# 05_Mechanicals.net
KiCad netlist of a schematic drawn in Altium Designer
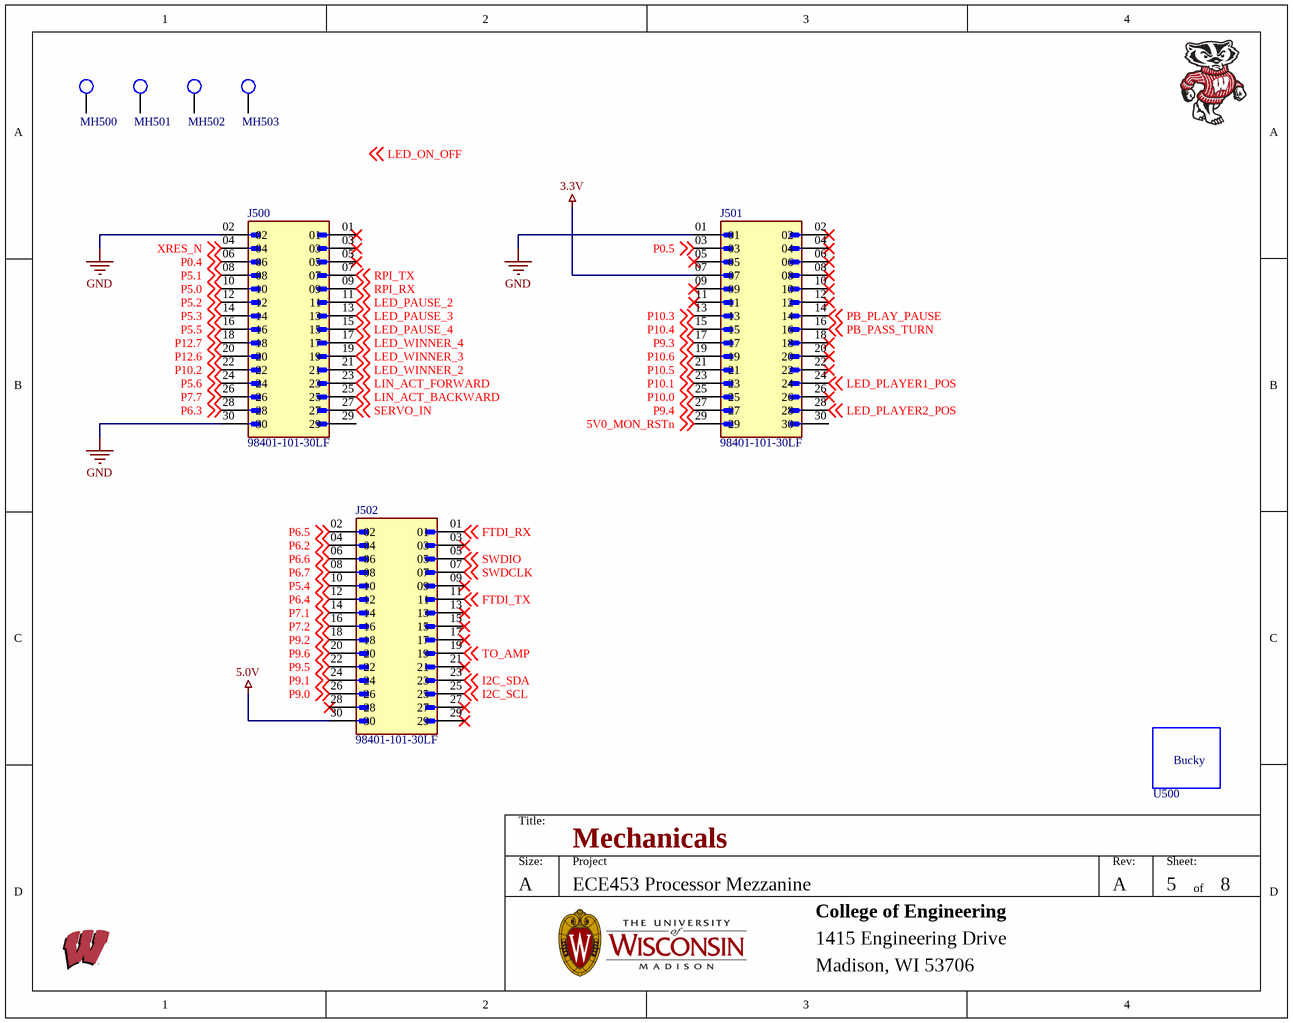
[diagram p0: 05_Mechanicals.SchDoc]

(export (version "E")
  (design (tool "Eeschema 10.0.6"))
  (components
    (comp (ref "J500")
      (value "98401-101-30LF")
      (footprint "AMPHENOL_98401-101-30LF")
      (description "Conn Unshrouded Header HDR 30 POS 2.54mm Solder ST SMD T/R")
      (fields (field (name "MF") "Amphenol ICC (FCI)") (field (name "MANUFACTURER") "Amphenol ICC / FCI"))
      (libsource (lib "98401-101-30LF") (part "98401-101-30LF"))
    )
    (comp (ref "J501")
      (value "98401-101-30LF")
      (footprint "AMPHENOL_98401-101-30LF")
      (description "Conn Unshrouded Header HDR 30 POS 2.54mm Solder ST SMD T/R")
      (fields (field (name "MF") "Amphenol ICC (FCI)") (field (name "MANUFACTURER") "Amphenol ICC / FCI"))
      (libsource (lib "98401-101-30LF") (part "98401-101-30LF"))
    )
    (comp (ref "J502")
      (value "98401-101-30LF")
      (footprint "AMPHENOL_98401-101-30LF")
      (description "Conn Unshrouded Header HDR 30 POS 2.54mm Solder ST SMD T/R")
      (fields (field (name "MF") "Amphenol ICC (FCI)") (field (name "MANUFACTURER") "Amphenol ICC / FCI"))
      (libsource (lib "98401-101-30LF") (part "98401-101-30LF"))
    )
    (comp (ref "MH500")
      (value "MHOLE_2_55MM")
      (footprint "MHOLE_2_55MM")
      (description "Mounting Holde")
      (fields (field (name "MANUFACTURER PART NUMBER") "UW MTHOLE"))
      (libsource (lib "ece315-2018-fall") (part "MHOLE_2_55MM"))
    )
    (comp (ref "MH501")
      (value "MHOLE_2_55MM")
      (footprint "MHOLE_2_55MM")
      (description "Mounting Holde")
      (fields (field (name "MANUFACTURER PART NUMBER") "UW MTHOLE"))
      (libsource (lib "ece315-2018-fall") (part "MHOLE_2_55MM"))
    )
    (comp (ref "MH502")
      (value "MHOLE_2_55MM")
      (footprint "MHOLE_2_55MM")
      (description "Mounting Holde")
      (fields (field (name "MANUFACTURER PART NUMBER") "UW MTHOLE"))
      (libsource (lib "ece315-2018-fall") (part "MHOLE_2_55MM"))
    )
    (comp (ref "MH503")
      (value "MHOLE_2_55MM")
      (footprint "MHOLE_2_55MM")
      (description "Mounting Holde")
      (fields (field (name "MANUFACTURER PART NUMBER") "UW MTHOLE"))
      (libsource (lib "ece315-2018-fall") (part "MHOLE_2_55MM"))
    )
    (comp (ref "U500")
      (value "Bucky")
      (footprint "WalkingBucky")
      (description "Bucky Badger Image")
      (fields (field (name "MANUFACTURER PART NUMBER") "UW Bucky"))
      (libsource (lib "ECE453") (part "Bucky"))
    )
  )
  (nets
    (net (code "1") (name "3.3V") (class "Default")
      (node (ref "J501") (pin "07") (pinfunction "07_07") (pintype "passive"))
    )
    (net (code "2") (name "5.0V") (class "Default")
      (node (ref "J502") (pin "30") (pinfunction "30_30") (pintype "passive"))
    )
    (net (code "3") (name "5V0_MON_RSTn") (class "Default")
      (node (ref "J501") (pin "29") (pinfunction "29_29") (pintype "passive"))
    )
    (net (code "4") (name "FTDI_RX") (class "Default")
      (node (ref "J502") (pin "01") (pinfunction "01_01") (pintype "passive"))
    )
    (net (code "5") (name "FTDI_TX") (class "Default")
      (node (ref "J502") (pin "11") (pinfunction "11_11") (pintype "passive"))
    )
    (net (code "6") (name "GND") (class "Default")
      (node (ref "J500") (pin "02") (pinfunction "02_02") (pintype "passive"))
      (node (ref "J500") (pin "30") (pinfunction "30_30") (pintype "passive"))
      (node (ref "J501") (pin "01") (pinfunction "01_01") (pintype "passive"))
    )
    (net (code "7") (name "I2C_SCL") (class "Default")
      (node (ref "J502") (pin "25") (pinfunction "25_25") (pintype "passive"))
    )
    (net (code "8") (name "I2C_SDA") (class "Default")
      (node (ref "J502") (pin "23") (pinfunction "23_23") (pintype "passive"))
    )
    (net (code "10") (name "LED_PAUSE_2") (class "Default")
      (node (ref "J500") (pin "11") (pinfunction "11_11") (pintype "passive"))
    )
    (net (code "11") (name "LED_PAUSE_3") (class "Default")
      (node (ref "J500") (pin "13") (pinfunction "13_13") (pintype "passive"))
    )
    (net (code "12") (name "LED_PAUSE_4") (class "Default")
      (node (ref "J500") (pin "15") (pinfunction "15_15") (pintype "passive"))
    )
    (net (code "13") (name "LED_PLAYER1_POS") (class "Default")
      (node (ref "J501") (pin "24") (pinfunction "24_24") (pintype "passive"))
    )
    (net (code "14") (name "LED_PLAYER2_POS") (class "Default")
      (node (ref "J501") (pin "28") (pinfunction "28_28") (pintype "passive"))
    )
    (net (code "15") (name "LED_WINNER_2") (class "Default")
      (node (ref "J500") (pin "21") (pinfunction "21_21") (pintype "passive"))
    )
    (net (code "16") (name "LED_WINNER_3") (class "Default")
      (node (ref "J500") (pin "19") (pinfunction "19_19") (pintype "passive"))
    )
    (net (code "17") (name "LED_WINNER_4") (class "Default")
      (node (ref "J500") (pin "17") (pinfunction "17_17") (pintype "passive"))
    )
    (net (code "18") (name "LIN_ACT_BACKWARD") (class "Default")
      (node (ref "J500") (pin "25") (pinfunction "25_25") (pintype "passive"))
    )
    (net (code "19") (name "LIN_ACT_FORWARD") (class "Default")
      (node (ref "J500") (pin "23") (pinfunction "23_23") (pintype "passive"))
    )
    (net (code "20") (name "P0.4") (class "Default")
      (node (ref "J500") (pin "06") (pinfunction "06_06") (pintype "passive"))
    )
    (net (code "21") (name "P0.5") (class "Default")
      (node (ref "J501") (pin "03") (pinfunction "03_03") (pintype "passive"))
    )
    (net (code "22") (name "P5.0") (class "Default")
      (node (ref "J500") (pin "10") (pinfunction "10_10") (pintype "passive"))
    )
    (net (code "23") (name "P5.1") (class "Default")
      (node (ref "J500") (pin "08") (pinfunction "08_08") (pintype "passive"))
    )
    (net (code "24") (name "P5.2") (class "Default")
      (node (ref "J500") (pin "12") (pinfunction "12_12") (pintype "passive"))
    )
    (net (code "25") (name "P5.3") (class "Default")
      (node (ref "J500") (pin "14") (pinfunction "14_14") (pintype "passive"))
    )
    (net (code "26") (name "P5.4") (class "Default")
      (node (ref "J502") (pin "10") (pinfunction "10_10") (pintype "passive"))
    )
    (net (code "27") (name "P5.5") (class "Default")
      (node (ref "J500") (pin "16") (pinfunction "16_16") (pintype "passive"))
    )
    (net (code "28") (name "P5.6") (class "Default")
      (node (ref "J500") (pin "24") (pinfunction "24_24") (pintype "passive"))
    )
    (net (code "29") (name "P6.2") (class "Default")
      (node (ref "J502") (pin "04") (pinfunction "04_04") (pintype "passive"))
    )
    (net (code "30") (name "P6.3") (class "Default")
      (node (ref "J500") (pin "28") (pinfunction "28_28") (pintype "passive"))
    )
    (net (code "31") (name "P6.4") (class "Default")
      (node (ref "J502") (pin "12") (pinfunction "12_12") (pintype "passive"))
    )
    (net (code "32") (name "P6.5") (class "Default")
      (node (ref "J502") (pin "02") (pinfunction "02_02") (pintype "passive"))
    )
    (net (code "33") (name "P6.6") (class "Default")
      (node (ref "J502") (pin "06") (pinfunction "06_06") (pintype "passive"))
    )
    (net (code "34") (name "P6.7") (class "Default")
      (node (ref "J502") (pin "08") (pinfunction "08_08") (pintype "passive"))
    )
    (net (code "35") (name "P7.1") (class "Default")
      (node (ref "J502") (pin "14") (pinfunction "14_14") (pintype "passive"))
    )
    (net (code "36") (name "P7.2") (class "Default")
      (node (ref "J502") (pin "16") (pinfunction "16_16") (pintype "passive"))
    )
    (net (code "37") (name "P7.7") (class "Default")
      (node (ref "J500") (pin "26") (pinfunction "26_26") (pintype "passive"))
    )
    (net (code "38") (name "P9.0") (class "Default")
      (node (ref "J502") (pin "26") (pinfunction "26_26") (pintype "passive"))
    )
    (net (code "39") (name "P9.1") (class "Default")
      (node (ref "J502") (pin "24") (pinfunction "24_24") (pintype "passive"))
    )
    (net (code "40") (name "P9.2") (class "Default")
      (node (ref "J502") (pin "18") (pinfunction "18_18") (pintype "passive"))
    )
    (net (code "41") (name "P9.3") (class "Default")
      (node (ref "J501") (pin "17") (pinfunction "17_17") (pintype "passive"))
    )
    (net (code "42") (name "P9.4") (class "Default")
      (node (ref "J501") (pin "27") (pinfunction "27_27") (pintype "passive"))
    )
    (net (code "43") (name "P9.5") (class "Default")
      (node (ref "J502") (pin "22") (pinfunction "22_22") (pintype "passive"))
    )
    (net (code "44") (name "P9.6") (class "Default")
      (node (ref "J502") (pin "20") (pinfunction "20_20") (pintype "passive"))
    )
    (net (code "45") (name "P10.0") (class "Default")
      (node (ref "J501") (pin "25") (pinfunction "25_25") (pintype "passive"))
    )
    (net (code "46") (name "P10.1") (class "Default")
      (node (ref "J501") (pin "23") (pinfunction "23_23") (pintype "passive"))
    )
    (net (code "47") (name "P10.2") (class "Default")
      (node (ref "J500") (pin "22") (pinfunction "22_22") (pintype "passive"))
    )
    (net (code "48") (name "P10.3") (class "Default")
      (node (ref "J501") (pin "13") (pinfunction "13_13") (pintype "passive"))
    )
    (net (code "49") (name "P10.4") (class "Default")
      (node (ref "J501") (pin "15") (pinfunction "15_15") (pintype "passive"))
    )
    (net (code "50") (name "P10.5") (class "Default")
      (node (ref "J501") (pin "21") (pinfunction "21_21") (pintype "passive"))
    )
    (net (code "51") (name "P10.6") (class "Default")
      (node (ref "J501") (pin "19") (pinfunction "19_19") (pintype "passive"))
    )
    (net (code "52") (name "P12.6") (class "Default")
      (node (ref "J500") (pin "20") (pinfunction "20_20") (pintype "passive"))
    )
    (net (code "53") (name "P12.7") (class "Default")
      (node (ref "J500") (pin "18") (pinfunction "18_18") (pintype "passive"))
    )
    (net (code "54") (name "PB_PASS_TURN") (class "Default")
      (node (ref "J501") (pin "16") (pinfunction "16_16") (pintype "passive"))
    )
    (net (code "55") (name "PB_PLAY_PAUSE") (class "Default")
      (node (ref "J501") (pin "14") (pinfunction "14_14") (pintype "passive"))
    )
    (net (code "56") (name "RPI_RX") (class "Default")
      (node (ref "J500") (pin "09") (pinfunction "09_09") (pintype "passive"))
    )
    (net (code "57") (name "RPI_TX") (class "Default")
      (node (ref "J500") (pin "07") (pinfunction "07_07") (pintype "passive"))
    )
    (net (code "58") (name "SERVO_IN") (class "Default")
      (node (ref "J500") (pin "27") (pinfunction "27_27") (pintype "passive"))
    )
    (net (code "59") (name "SWDCLK") (class "Default")
      (node (ref "J502") (pin "07") (pinfunction "07_07") (pintype "passive"))
    )
    (net (code "60") (name "SWDIO") (class "Default")
      (node (ref "J502") (pin "05") (pinfunction "05_05") (pintype "passive"))
    )
    (net (code "61") (name "TO_AMP") (class "Default")
      (node (ref "J502") (pin "19") (pinfunction "19_19") (pintype "passive"))
    )
    (net (code "62") (name "XRES_N") (class "Default")
      (node (ref "J500") (pin "04") (pinfunction "04_04") (pintype "passive"))
    )
    (net (code "63") (name "unconnected-(J500-Pad01)") (class "Default")
      (node (ref "J500") (pin "01") (pinfunction "01_01") (pintype "passive+no_connect"))
    )
    (net (code "64") (name "unconnected-(J500-Pad03)") (class "Default")
      (node (ref "J500") (pin "03") (pinfunction "03_03") (pintype "passive+no_connect"))
    )
    (net (code "65") (name "unconnected-(J500-Pad05)") (class "Default")
      (node (ref "J500") (pin "05") (pinfunction "05_05") (pintype "passive+no_connect"))
    )
    (net (code "66") (name "unconnected-(J500-Pad29)") (class "Default")
      (node (ref "J500") (pin "29") (pinfunction "29_29") (pintype "passive"))
    )
    (net (code "67") (name "unconnected-(J501-Pad02)") (class "Default")
      (node (ref "J501") (pin "02") (pinfunction "02_02") (pintype "passive+no_connect"))
    )
    (net (code "68") (name "unconnected-(J501-Pad04)") (class "Default")
      (node (ref "J501") (pin "04") (pinfunction "04_04") (pintype "passive+no_connect"))
    )
    (net (code "69") (name "unconnected-(J501-Pad05)") (class "Default")
      (node (ref "J501") (pin "05") (pinfunction "05_05") (pintype "passive+no_connect"))
    )
    (net (code "70") (name "unconnected-(J501-Pad06)") (class "Default")
      (node (ref "J501") (pin "06") (pinfunction "06_06") (pintype "passive+no_connect"))
    )
    (net (code "71") (name "unconnected-(J501-Pad08)") (class "Default")
      (node (ref "J501") (pin "08") (pinfunction "08_08") (pintype "passive+no_connect"))
    )
    (net (code "72") (name "unconnected-(J501-Pad09)") (class "Default")
      (node (ref "J501") (pin "09") (pinfunction "09_09") (pintype "passive+no_connect"))
    )
    (net (code "73") (name "unconnected-(J501-Pad10)") (class "Default")
      (node (ref "J501") (pin "10") (pinfunction "10_10") (pintype "passive+no_connect"))
    )
    (net (code "74") (name "unconnected-(J501-Pad11)") (class "Default")
      (node (ref "J501") (pin "11") (pinfunction "11_11") (pintype "passive+no_connect"))
    )
    (net (code "75") (name "unconnected-(J501-Pad12)") (class "Default")
      (node (ref "J501") (pin "12") (pinfunction "12_12") (pintype "passive+no_connect"))
    )
    (net (code "76") (name "unconnected-(J501-Pad18)") (class "Default")
      (node (ref "J501") (pin "18") (pinfunction "18_18") (pintype "passive+no_connect"))
    )
    (net (code "77") (name "unconnected-(J501-Pad20)") (class "Default")
      (node (ref "J501") (pin "20") (pinfunction "20_20") (pintype "passive+no_connect"))
    )
    (net (code "78") (name "unconnected-(J501-Pad22)") (class "Default")
      (node (ref "J501") (pin "22") (pinfunction "22_22") (pintype "passive+no_connect"))
    )
    (net (code "79") (name "unconnected-(J501-Pad26)") (class "Default")
      (node (ref "J501") (pin "26") (pinfunction "26_26") (pintype "passive+no_connect"))
    )
    (net (code "80") (name "unconnected-(J501-Pad30)") (class "Default")
      (node (ref "J501") (pin "30") (pinfunction "30_30") (pintype "passive"))
    )
    (net (code "81") (name "unconnected-(J502-Pad03)") (class "Default")
      (node (ref "J502") (pin "03") (pinfunction "03_03") (pintype "passive+no_connect"))
    )
    (net (code "82") (name "unconnected-(J502-Pad09)") (class "Default")
      (node (ref "J502") (pin "09") (pinfunction "09_09") (pintype "passive+no_connect"))
    )
    (net (code "83") (name "unconnected-(J502-Pad13)") (class "Default")
      (node (ref "J502") (pin "13") (pinfunction "13_13") (pintype "passive+no_connect"))
    )
    (net (code "84") (name "unconnected-(J502-Pad15)") (class "Default")
      (node (ref "J502") (pin "15") (pinfunction "15_15") (pintype "passive+no_connect"))
    )
    (net (code "85") (name "unconnected-(J502-Pad17)") (class "Default")
      (node (ref "J502") (pin "17") (pinfunction "17_17") (pintype "passive+no_connect"))
    )
    (net (code "86") (name "unconnected-(J502-Pad21)") (class "Default")
      (node (ref "J502") (pin "21") (pinfunction "21_21") (pintype "passive+no_connect"))
    )
    (net (code "87") (name "unconnected-(J502-Pad27)") (class "Default")
      (node (ref "J502") (pin "27") (pinfunction "27_27") (pintype "passive+no_connect"))
    )
    (net (code "88") (name "unconnected-(J502-Pad28)") (class "Default")
      (node (ref "J502") (pin "28") (pinfunction "28_28") (pintype "passive+no_connect"))
    )
    (net (code "89") (name "unconnected-(J502-Pad29)") (class "Default")
      (node (ref "J502") (pin "29") (pinfunction "29_29") (pintype "passive+no_connect"))
    )
    (net (code "90") (name "unconnected-(MH500-Pad1)") (class "Default")
      (node (ref "MH500") (pin "1") (pintype "passive"))
    )
    (net (code "91") (name "unconnected-(MH501-Pad1)") (class "Default")
      (node (ref "MH501") (pin "1") (pintype "passive"))
    )
    (net (code "92") (name "unconnected-(MH502-Pad1)") (class "Default")
      (node (ref "MH502") (pin "1") (pintype "passive"))
    )
    (net (code "93") (name "unconnected-(MH503-Pad1)") (class "Default")
      (node (ref "MH503") (pin "1") (pintype "passive"))
    )
  )
)
